# twister.net
KiCad netlist of a schematic drawn in EAGLE
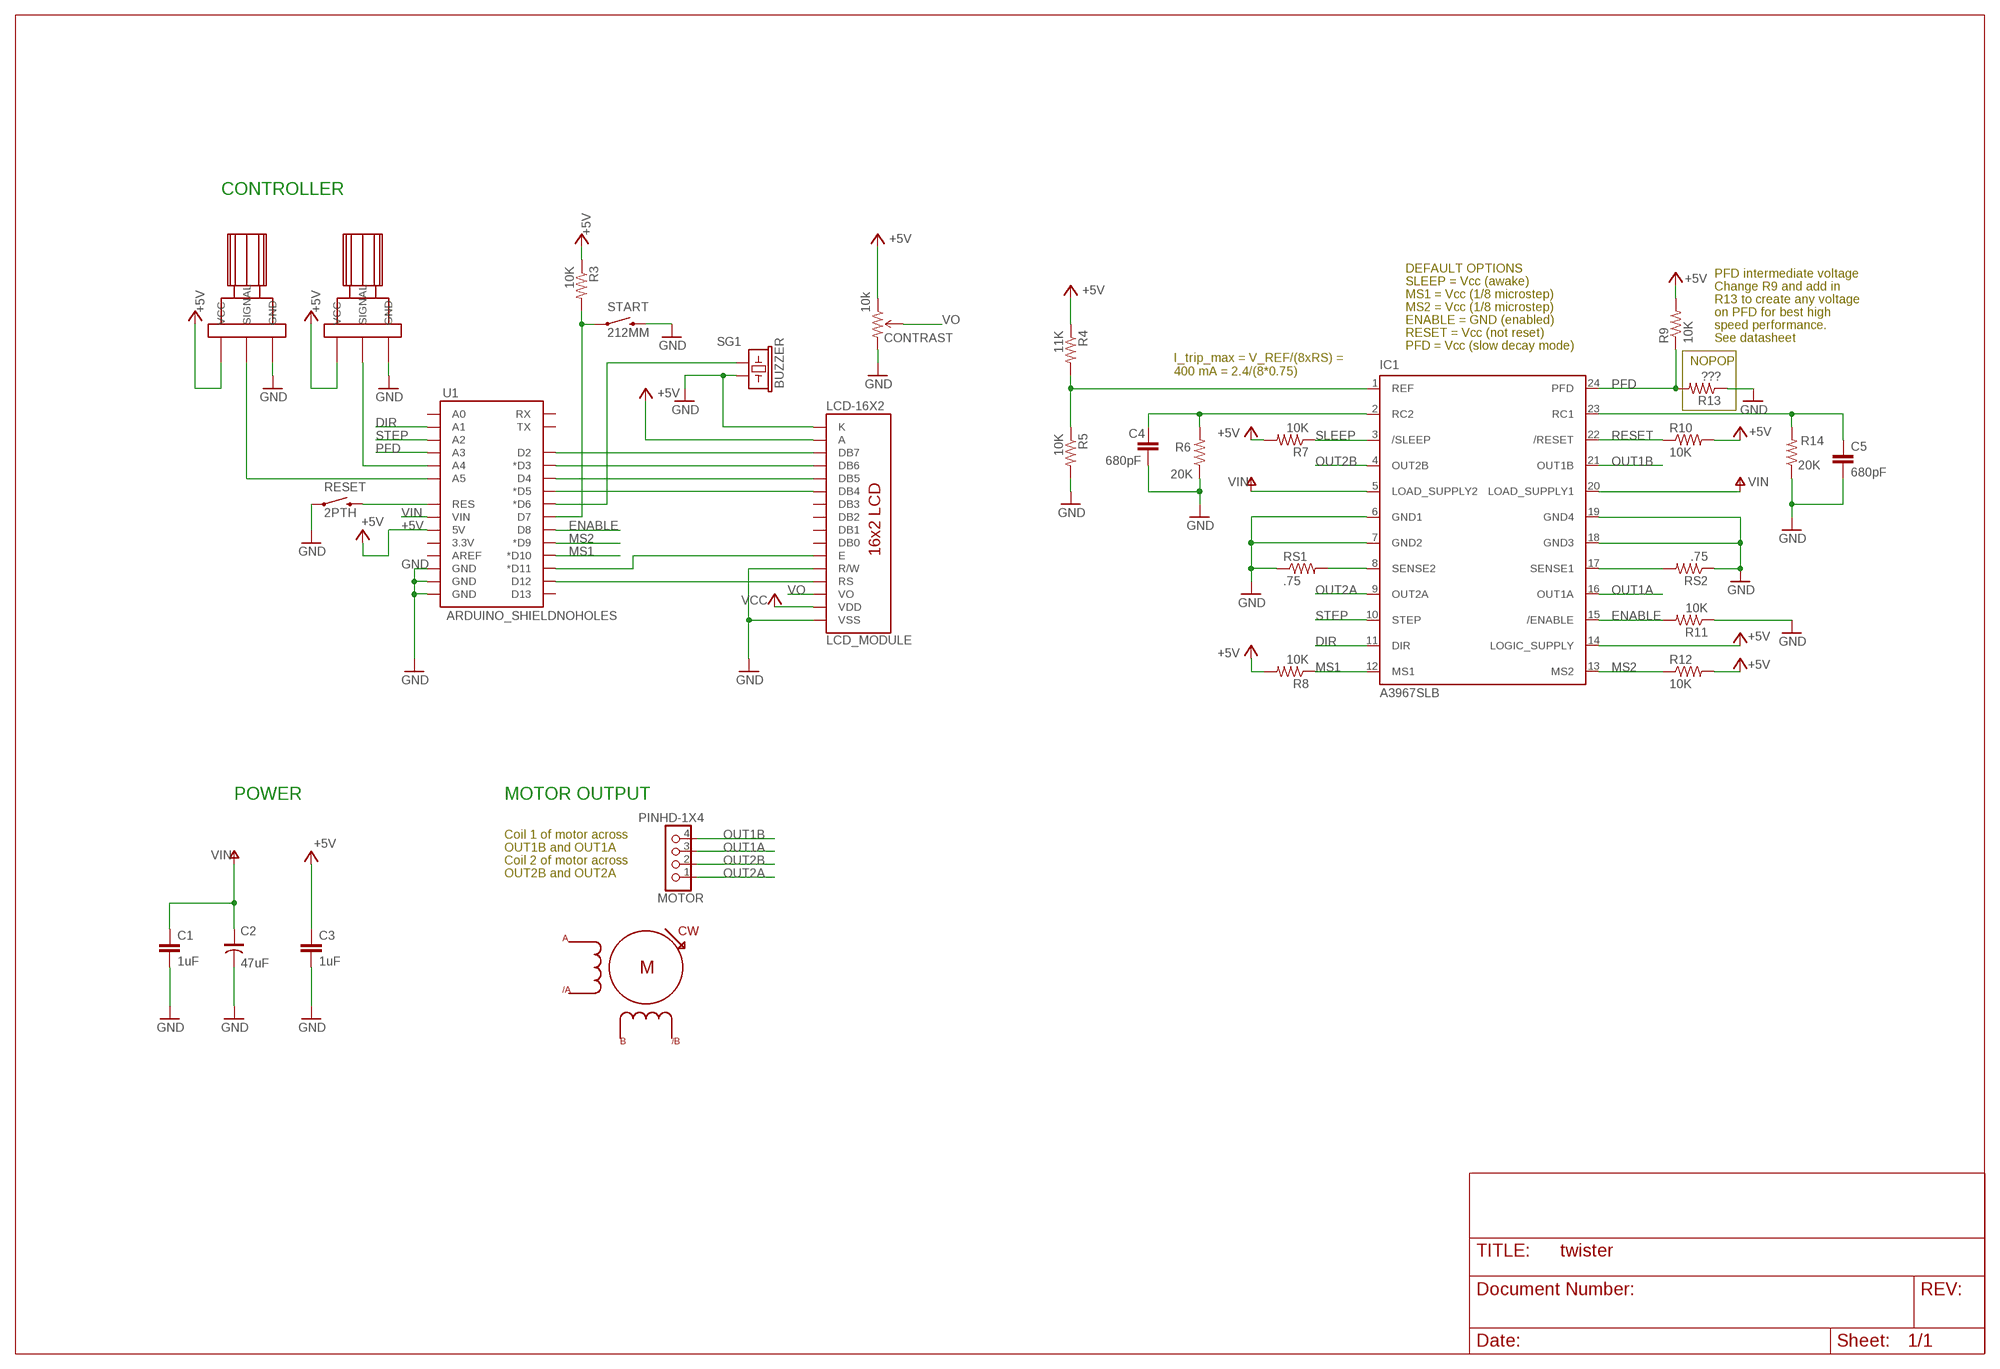
[diagram p0: schematic, sheet 1]

(export (version "E")
  (design (tool "Eeschema 10.0.6"))
  (components
    (comp (ref "BUZZER")
      (value "SG1")
      (footprint "eagle-import:BUZZER-12MM")
      (libsource (lib "eagle-import") (part "BUZZERPTH"))
    )
    (comp (ref "C1")
      (value "1uF")
      (footprint "eagle-import:0805")
      (fields (field (name "PARTNO") "C2012X5R1Cxxxxxxx"))
      (libsource (lib "eagle-import") (part "C_0805"))
    )
    (comp (ref "C2")
      (value "47uF")
      (footprint "eagle-import:153CLV-0807")
      (libsource (lib "eagle-import") (part "C-POL_0807"))
    )
    (comp (ref "C3")
      (value "1uF")
      (footprint "eagle-import:0805")
      (fields (field (name "PARTNO") "C2012X5R1Cxxxxxxx"))
      (libsource (lib "eagle-import") (part "C_0805"))
    )
    (comp (ref "C4")
      (value "680pF")
      (footprint "eagle-import:0603")
      (libsource (lib "eagle-import") (part "C_0603"))
    )
    (comp (ref "C5")
      (value "680pF")
      (footprint "eagle-import:0603")
      (libsource (lib "eagle-import") (part "C_0603"))
    )
    (comp (ref "CONTRAST")
      (value "10k")
      (footprint "eagle-import:3362U-2")
      (libsource (lib "eagle-import") (part "TRIMPOT"))
    )
    (comp (ref "IC1")
      (value "A3967SLB")
      (footprint "eagle-import:SO24W")
      (libsource (lib "eagle-import") (part "A3967SLB"))
    )
    (comp (ref "LCD_MODULE")
      (value "LCD-16X2")
      (footprint "eagle-import:LCD-16X2")
      (libsource (lib "eagle-import") (part "LCD-16X2"))
    )
    (comp (ref "MOTOR")
      (value "PINHD-1X4")
      (footprint "eagle-import:1X04")
      (libsource (lib "eagle-import") (part "PINHD-1X4"))
    )
    (comp (ref "R1")
      (value "R12-0")
      (footprint "eagle-import:LARGE_POT")
      (libsource (lib "eagle-import") (part "LARGE_POT"))
    )
    (comp (ref "R2")
      (value "R12-0")
      (footprint "eagle-import:LARGE_POT")
      (libsource (lib "eagle-import") (part "LARGE_POT"))
    )
    (comp (ref "R3")
      (value "10K")
      (footprint "eagle-import:0603")
      (fields (field (name "MPN") "ERJ-3EKFxxxxV"))
      (libsource (lib "eagle-import") (part "R_0603"))
    )
    (comp (ref "R4")
      (value "11K")
      (footprint "eagle-import:0603")
      (fields (field (name "MPN") "ERJ-3EKFxxxxV"))
      (libsource (lib "eagle-import") (part "R_0603"))
    )
    (comp (ref "R5")
      (value "10K")
      (footprint "eagle-import:0603")
      (fields (field (name "MPN") "ERJ-3EKFxxxxV"))
      (libsource (lib "eagle-import") (part "R_0603"))
    )
    (comp (ref "R6")
      (value "20K")
      (footprint "eagle-import:0603")
      (fields (field (name "MPN") "ERJ-3EKFxxxxV"))
      (libsource (lib "eagle-import") (part "R_0603"))
    )
    (comp (ref "R7")
      (value "10K")
      (footprint "eagle-import:0603")
      (fields (field (name "MPN") "ERJ-3EKFxxxxV"))
      (libsource (lib "eagle-import") (part "R_0603"))
    )
    (comp (ref "R8")
      (value "10K")
      (footprint "eagle-import:0603")
      (fields (field (name "MPN") "ERJ-3EKFxxxxV"))
      (libsource (lib "eagle-import") (part "R_0603"))
    )
    (comp (ref "R9")
      (value "10K")
      (footprint "eagle-import:0603")
      (fields (field (name "MPN") "ERJ-3EKFxxxxV"))
      (libsource (lib "eagle-import") (part "R_0603"))
    )
    (comp (ref "R10")
      (value "10K")
      (footprint "eagle-import:0603")
      (fields (field (name "MPN") "ERJ-3EKFxxxxV"))
      (libsource (lib "eagle-import") (part "R_0603"))
    )
    (comp (ref "R11")
      (value "10K")
      (footprint "eagle-import:0603")
      (fields (field (name "MPN") "ERJ-3EKFxxxxV"))
      (libsource (lib "eagle-import") (part "R_0603"))
    )
    (comp (ref "R12")
      (value "10K")
      (footprint "eagle-import:0603")
      (fields (field (name "MPN") "ERJ-3EKFxxxxV"))
      (libsource (lib "eagle-import") (part "R_0603"))
    )
    (comp (ref "R13")
      (value "???")
      (footprint "eagle-import:0603")
      (fields (field (name "MPN") "ERJ-3EKFxxxxV"))
      (libsource (lib "eagle-import") (part "R_0603"))
    )
    (comp (ref "R14")
      (value "20K")
      (footprint "eagle-import:0603")
      (fields (field (name "MPN") "ERJ-3EKFxxxxV"))
      (libsource (lib "eagle-import") (part "R_0603"))
    )
    (comp (ref "RESET")
      (value "2PTH")
      (footprint "eagle-import:TACTILE-PTH")
      (libsource (lib "eagle-import") (part "SWITCH-MOMENTARY-2PTH"))
    )
    (comp (ref "RS1")
      (value ".75")
      (footprint "eagle-import:1206")
      (libsource (lib "eagle-import") (part "R_1206"))
    )
    (comp (ref "RS2")
      (value ".75")
      (footprint "eagle-import:1206")
      (libsource (lib "eagle-import") (part "R_1206"))
    )
    (comp (ref "START")
      (value "212MM")
      (footprint "eagle-import:TACTILE-PTH-12MM")
      (libsource (lib "eagle-import") (part "SWITCH-MOMENTARY-212MM"))
    )
    (comp (ref "STEPPER")
      (value "ST-PM35")
      (footprint "eagle-import:ST-PM35-15-11C")
      (libsource (lib "eagle-import") (part "STEPPER_ST-PM35"))
    )
    (comp (ref "U1")
      (value "ARDUINO_SHIELDNOHOLES")
      (footprint "eagle-import:DUEMILANOVE_SHIELD_NOHOLES")
      (libsource (lib "eagle-import") (part "ARDUINO_SHIELDNOHOLES"))
    )
  )
  (nets
    (net (code "1") (name "+5V") (class "Default")
      (node (ref "C3") (pin "1") (pinfunction "1_1") (pintype "passive"))
      (node (ref "CONTRAST") (pin "1") (pinfunction "CCW_1") (pintype "passive"))
      (node (ref "IC1") (pin "14") (pinfunction "LOGIC_SUPPLY_14") (pintype "tri_state"))
      (node (ref "LCD_MODULE") (pin "15") (pinfunction "A_15") (pintype "power_in"))
      (node (ref "LCD_MODULE") (pin "2") (pinfunction "VDD_2") (pintype "power_in"))
      (node (ref "R1") (pin "LEFT") (pinfunction "VCC_LEFT") (pintype "bidirectional"))
      (node (ref "R10") (pin "2") (pinfunction "2_2") (pintype "passive"))
      (node (ref "R12") (pin "2") (pinfunction "2_2") (pintype "passive"))
      (node (ref "R2") (pin "LEFT") (pinfunction "VCC_LEFT") (pintype "bidirectional"))
      (node (ref "R3") (pin "1") (pinfunction "1_1") (pintype "passive"))
      (node (ref "R4") (pin "1") (pinfunction "1_1") (pintype "passive"))
      (node (ref "R7") (pin "2") (pinfunction "2_2") (pintype "passive"))
      (node (ref "R8") (pin "2") (pinfunction "2_2") (pintype "passive"))
      (node (ref "R9") (pin "2") (pinfunction "2_2") (pintype "passive"))
      (node (ref "U1") (pin "5V") (pinfunction "5V_5V") (pintype "bidirectional"))
    )
    (net (code "2") (name "/DIR") (class "Default")
      (node (ref "IC1") (pin "11") (pinfunction "DIR_11") (pintype "power_in"))
      (node (ref "U1") (pin "A1") (pinfunction "A1_A1") (pintype "bidirectional"))
    )
    (net (code "3") (name "/ENABLE") (class "Default")
      (node (ref "IC1") (pin "15") (pinfunction "/ENABLE_15") (pintype "tri_state"))
      (node (ref "R11") (pin "2") (pinfunction "2_2") (pintype "passive"))
      (node (ref "U1") (pin "D8") (pinfunction "D8_D8") (pintype "bidirectional"))
    )
    (net (code "4") (name "/MS1") (class "Default")
      (node (ref "IC1") (pin "12") (pinfunction "MS1_12") (pintype "output"))
      (node (ref "R8") (pin "1") (pinfunction "1_1") (pintype "passive"))
      (node (ref "U1") (pin "D10") (pinfunction "*D10_D10") (pintype "bidirectional"))
    )
    (net (code "5") (name "/MS2") (class "Default")
      (node (ref "IC1") (pin "13") (pinfunction "MS2_13") (pintype "tri_state"))
      (node (ref "R12") (pin "1") (pinfunction "1_1") (pintype "passive"))
      (node (ref "U1") (pin "D9") (pinfunction "*D9_D9") (pintype "bidirectional"))
    )
    (net (code "6") (name "/OUT1A") (class "Default")
      (node (ref "IC1") (pin "16") (pinfunction "OUT1A_16") (pintype "tri_state"))
      (node (ref "MOTOR") (pin "3") (pinfunction "3_3") (pintype "passive"))
    )
    (net (code "7") (name "/OUT1B") (class "Default")
      (node (ref "IC1") (pin "21") (pinfunction "OUT1B_21") (pintype "tri_state"))
      (node (ref "MOTOR") (pin "4") (pinfunction "4_4") (pintype "passive"))
    )
    (net (code "8") (name "/OUT2A") (class "Default")
      (node (ref "IC1") (pin "9") (pinfunction "OUT2A_9") (pintype "power_in"))
      (node (ref "MOTOR") (pin "1") (pinfunction "1_1") (pintype "passive"))
    )
    (net (code "9") (name "/OUT2B") (class "Default")
      (node (ref "IC1") (pin "4") (pinfunction "OUT2B_4") (pintype "passive"))
      (node (ref "MOTOR") (pin "2") (pinfunction "2_2") (pintype "passive"))
    )
    (net (code "10") (name "/PFD") (class "Default")
      (node (ref "IC1") (pin "24") (pinfunction "PFD_24") (pintype "tri_state"))
      (node (ref "R13") (pin "2") (pinfunction "2_2") (pintype "passive"))
      (node (ref "R9") (pin "1") (pinfunction "1_1") (pintype "passive"))
      (node (ref "U1") (pin "A3") (pinfunction "A3_A3") (pintype "bidirectional"))
    )
    (net (code "11") (name "/RESET") (class "Default")
      (node (ref "IC1") (pin "22") (pinfunction "/RESET_22") (pintype "tri_state"))
      (node (ref "R10") (pin "1") (pinfunction "1_1") (pintype "passive"))
      (node (ref "RESET") (pin "3") (pinfunction "2_3") (pintype "passive"))
      (node (ref "U1") (pin "RES") (pinfunction "RES_RES") (pintype "bidirectional"))
    )
    (net (code "12") (name "/SLEEP") (class "Default")
      (node (ref "IC1") (pin "3") (pinfunction "/SLEEP_3") (pintype "passive"))
      (node (ref "R7") (pin "1") (pinfunction "1_1") (pintype "passive"))
    )
    (net (code "13") (name "/STEP") (class "Default")
      (node (ref "IC1") (pin "10") (pinfunction "STEP_10") (pintype "power_in"))
      (node (ref "U1") (pin "A2") (pinfunction "A2_A2") (pintype "bidirectional"))
    )
    (net (code "14") (name "/VO") (class "Default")
      (node (ref "CONTRAST") (pin "2") (pinfunction "WIPER_2") (pintype "passive"))
      (node (ref "LCD_MODULE") (pin "3") (pinfunction "VO_3") (pintype "bidirectional"))
    )
    (net (code "15") (name "GND") (class "Default")
      (node (ref "BUZZER") (pin "+") (pinfunction "1_+") (pintype "passive"))
      (node (ref "C1") (pin "2") (pinfunction "2_2") (pintype "passive"))
      (node (ref "C2") (pin "-") (pinfunction "-_-") (pintype "passive"))
      (node (ref "C3") (pin "2") (pinfunction "2_2") (pintype "passive"))
      (node (ref "C4") (pin "2") (pinfunction "2_2") (pintype "passive"))
      (node (ref "C5") (pin "2") (pinfunction "2_2") (pintype "passive"))
      (node (ref "CONTRAST") (pin "3") (pinfunction "CW_3") (pintype "passive"))
      (node (ref "IC1") (pin "18") (pinfunction "GND3_18") (pintype "power_in"))
      (node (ref "IC1") (pin "19") (pinfunction "GND4_19") (pintype "power_in"))
      (node (ref "IC1") (pin "6") (pinfunction "GND1_6") (pintype "power_in"))
      (node (ref "IC1") (pin "7") (pinfunction "GND2_7") (pintype "power_in"))
      (node (ref "LCD_MODULE") (pin "1") (pinfunction "VSS_1") (pintype "power_in"))
      (node (ref "LCD_MODULE") (pin "16") (pinfunction "K_16") (pintype "power_in"))
      (node (ref "LCD_MODULE") (pin "5") (pinfunction "R/W_5") (pintype "input"))
      (node (ref "R1") (pin "RIGHT") (pinfunction "GND_RIGHT") (pintype "bidirectional"))
      (node (ref "R11") (pin "1") (pinfunction "1_1") (pintype "passive"))
      (node (ref "R13") (pin "1") (pinfunction "1_1") (pintype "passive"))
      (node (ref "R14") (pin "1") (pinfunction "1_1") (pintype "passive"))
      (node (ref "R2") (pin "RIGHT") (pinfunction "GND_RIGHT") (pintype "bidirectional"))
      (node (ref "R5") (pin "2") (pinfunction "2_2") (pintype "passive"))
      (node (ref "R6") (pin "1") (pinfunction "1_1") (pintype "passive"))
      (node (ref "RESET") (pin "1") (pinfunction "1_1") (pintype "passive"))
      (node (ref "RS1") (pin "1") (pinfunction "1_1") (pintype "passive"))
      (node (ref "RS2") (pin "1") (pinfunction "1_1") (pintype "passive"))
      (node (ref "START") (pin "3") (pinfunction "2_3") (pintype "passive"))
      (node (ref "U1") (pin "GND@0") (pinfunction "GND_GND@0") (pintype "bidirectional"))
      (node (ref "U1") (pin "GND@1") (pinfunction "GND_GND@1") (pintype "bidirectional"))
      (node (ref "U1") (pin "GND@2") (pinfunction "GND_GND@2") (pintype "bidirectional"))
    )
    (net (code "16") (name "Net-(BUZZER-2)") (class "Default")
      (node (ref "BUZZER") (pin "-") (pinfunction "2_-") (pintype "passive"))
      (node (ref "U1") (pin "D6") (pinfunction "*D6_D6") (pintype "bidirectional"))
    )
    (net (code "17") (name "Net-(IC1-RC1)") (class "Default")
      (node (ref "C5") (pin "1") (pinfunction "1_1") (pintype "passive"))
      (node (ref "IC1") (pin "23") (pinfunction "RC1_23") (pintype "tri_state"))
      (node (ref "R14") (pin "2") (pinfunction "2_2") (pintype "passive"))
    )
    (net (code "18") (name "Net-(IC1-RC2)") (class "Default")
      (node (ref "C4") (pin "1") (pinfunction "1_1") (pintype "passive"))
      (node (ref "IC1") (pin "2") (pinfunction "RC2_2") (pintype "input"))
      (node (ref "R6") (pin "2") (pinfunction "2_2") (pintype "passive"))
    )
    (net (code "19") (name "Net-(IC1-REF)") (class "Default")
      (node (ref "IC1") (pin "1") (pinfunction "REF_1") (pintype "bidirectional"))
      (node (ref "R4") (pin "2") (pinfunction "2_2") (pintype "passive"))
      (node (ref "R5") (pin "1") (pinfunction "1_1") (pintype "passive"))
    )
    (net (code "20") (name "Net-(IC1-SENSE1)") (class "Default")
      (node (ref "IC1") (pin "17") (pinfunction "SENSE1_17") (pintype "tri_state"))
      (node (ref "RS2") (pin "2") (pinfunction "2_2") (pintype "passive"))
    )
    (net (code "21") (name "Net-(IC1-SENSE2)") (class "Default")
      (node (ref "IC1") (pin "8") (pinfunction "SENSE2_8") (pintype "input"))
      (node (ref "RS1") (pin "2") (pinfunction "2_2") (pintype "passive"))
    )
    (net (code "22") (name "Net-(LCD_MODULE-DB4)") (class "Default")
      (node (ref "LCD_MODULE") (pin "11") (pinfunction "DB4_11") (pintype "bidirectional"))
      (node (ref "U1") (pin "D5") (pinfunction "*D5_D5") (pintype "bidirectional"))
    )
    (net (code "23") (name "Net-(LCD_MODULE-DB5)") (class "Default")
      (node (ref "LCD_MODULE") (pin "12") (pinfunction "DB5_12") (pintype "bidirectional"))
      (node (ref "U1") (pin "D4") (pinfunction "D4_D4") (pintype "bidirectional"))
    )
    (net (code "24") (name "Net-(LCD_MODULE-DB6)") (class "Default")
      (node (ref "LCD_MODULE") (pin "13") (pinfunction "DB6_13") (pintype "bidirectional"))
      (node (ref "U1") (pin "D3") (pinfunction "*D3_D3") (pintype "bidirectional"))
    )
    (net (code "25") (name "Net-(LCD_MODULE-DB7)") (class "Default")
      (node (ref "LCD_MODULE") (pin "14") (pinfunction "DB7_14") (pintype "bidirectional"))
      (node (ref "U1") (pin "D2") (pinfunction "D2_D2") (pintype "bidirectional"))
    )
    (net (code "26") (name "Net-(LCD_MODULE-E)") (class "Default")
      (node (ref "LCD_MODULE") (pin "6") (pinfunction "E_6") (pintype "input"))
      (node (ref "U1") (pin "D11") (pinfunction "*D11_D11") (pintype "bidirectional"))
    )
    (net (code "27") (name "Net-(LCD_MODULE-RS)") (class "Default")
      (node (ref "LCD_MODULE") (pin "4") (pinfunction "RS_4") (pintype "input"))
      (node (ref "U1") (pin "D12") (pinfunction "D12_D12") (pintype "bidirectional"))
    )
    (net (code "28") (name "Net-(R1-SIGNAL)") (class "Default")
      (node (ref "R1") (pin "CENTER") (pinfunction "SIGNAL_CENTER") (pintype "bidirectional"))
      (node (ref "U1") (pin "A5") (pinfunction "A5_A5") (pintype "bidirectional"))
    )
    (net (code "29") (name "Net-(R2-SIGNAL)") (class "Default")
      (node (ref "R2") (pin "CENTER") (pinfunction "SIGNAL_CENTER") (pintype "bidirectional"))
      (node (ref "U1") (pin "A4") (pinfunction "A4_A4") (pintype "bidirectional"))
    )
    (net (code "30") (name "Net-(R3-Pad2)") (class "Default")
      (node (ref "R3") (pin "2") (pinfunction "2_2") (pintype "passive"))
      (node (ref "START") (pin "1") (pinfunction "1_1") (pintype "passive"))
      (node (ref "U1") (pin "D7") (pinfunction "D7_D7") (pintype "bidirectional"))
    )
    (net (code "31") (name "VIN") (class "Default")
      (node (ref "C1") (pin "1") (pinfunction "1_1") (pintype "passive"))
      (node (ref "C2") (pin "+") (pinfunction "+_+") (pintype "passive"))
      (node (ref "IC1") (pin "20") (pinfunction "LOAD_SUPPLY1_20") (pintype "tri_state"))
      (node (ref "IC1") (pin "5") (pinfunction "LOAD_SUPPLY2_5") (pintype "passive"))
      (node (ref "U1") (pin "VIN") (pinfunction "VIN_VIN") (pintype "bidirectional"))
    )
    (net (code "32") (name "unconnected-(LCD_MODULE-DB0-Pad7)") (class "Default")
      (node (ref "LCD_MODULE") (pin "7") (pinfunction "DB0_7") (pintype "bidirectional"))
    )
    (net (code "33") (name "unconnected-(LCD_MODULE-DB1-Pad8)") (class "Default")
      (node (ref "LCD_MODULE") (pin "8") (pinfunction "DB1_8") (pintype "bidirectional"))
    )
    (net (code "34") (name "unconnected-(LCD_MODULE-DB2-Pad9)") (class "Default")
      (node (ref "LCD_MODULE") (pin "9") (pinfunction "DB2_9") (pintype "bidirectional"))
    )
    (net (code "35") (name "unconnected-(LCD_MODULE-DB3-Pad10)") (class "Default")
      (node (ref "LCD_MODULE") (pin "10") (pinfunction "DB3_10") (pintype "bidirectional"))
    )
    (net (code "36") (name "unconnected-(U1-Pad3.3V)") (class "Default")
      (node (ref "U1") (pin "3.3V") (pinfunction "3.3V_3.3V") (pintype "bidirectional"))
    )
    (net (code "37") (name "unconnected-(U1-PadA0)") (class "Default")
      (node (ref "U1") (pin "A0") (pinfunction "A0_A0") (pintype "bidirectional"))
    )
    (net (code "38") (name "unconnected-(U1-PadAREF)") (class "Default")
      (node (ref "U1") (pin "AREF") (pinfunction "AREF_AREF") (pintype "bidirectional"))
    )
    (net (code "39") (name "unconnected-(U1-PadD13)") (class "Default")
      (node (ref "U1") (pin "D13") (pinfunction "D13_D13") (pintype "bidirectional"))
    )
    (net (code "40") (name "unconnected-(U1-PadRX)") (class "Default")
      (node (ref "U1") (pin "RX") (pinfunction "RX_RX") (pintype "bidirectional"))
    )
    (net (code "41") (name "unconnected-(U1-PadTX)") (class "Default")
      (node (ref "U1") (pin "TX") (pinfunction "TX_TX") (pintype "bidirectional"))
    )
  )
)
